# MCU.net
KiCad netlist of a schematic drawn in Altium Designer
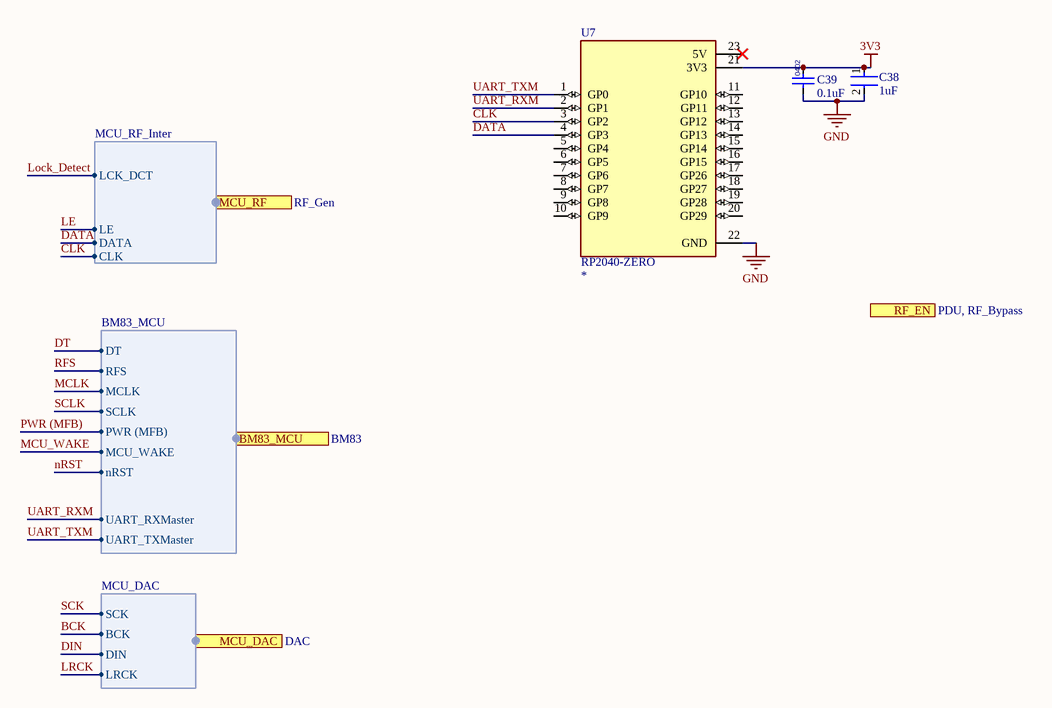
[diagram p0: MCU.SchDoc]

(export (version "E")
  (design (tool "Eeschema 10.0.6"))
  (components
    (comp (ref "C38")
      (value "1uF")
      (footprint "FP-GRM155-0_1-IPC_C")
      (libsource (lib "Altium Content Vault") (part "11868f565c42a9108669ba33697ecf6"))
    )
    (comp (ref "C39")
      (value "0.1uF")
      (footprint "FP-CC0402-IPC_B")
      (fields (field (name "TOLERANCE") "10%"))
      (libsource (lib "University of Wisconsin Formula FSAE") (part "0402 ceramic cap"))
    )
    (comp (ref "U7")
      (value "RP2040-ZERO")
      (footprint "MODULE_RP2040-ZERO")
      (description "Low-Cost, High-Performance Pico-Like MCU Board Based On Raspberry Pi Microcontroller RP2040")
      (fields (field (name "ALTIUM_VALUE") "*") (field (name "MF") "Waveshare Electronics"))
      (libsource (lib "University of Wisconsin Formula FSAE") (part "RP2040-ZERO"))
    )
  )
  (nets
    (net (code "5") (name "/CLK") (class "Default")
      (node (ref "U7") (pin "3") (pinfunction "GP2_3") (pintype "bidirectional"))
    )
    (net (code "6") (name "/DATA") (class "Default")
      (node (ref "U7") (pin "4") (pinfunction "GP3_4") (pintype "bidirectional"))
    )
    (net (code "19") (name "/UART_RXM") (class "Default")
      (node (ref "U7") (pin "2") (pinfunction "GP1_2") (pintype "bidirectional"))
    )
    (net (code "20") (name "/UART_TXM") (class "Default")
      (node (ref "U7") (pin "1") (pinfunction "GP0_1") (pintype "bidirectional"))
    )
    (net (code "25") (name "3V3") (class "Default")
      (node (ref "C38") (pin "1") (pinfunction "1_1") (pintype "passive"))
      (node (ref "C39") (pin "2") (pinfunction "2_2") (pintype "passive"))
      (node (ref "U7") (pin "21") (pinfunction "3V3_21") (pintype "power_in"))
    )
    (net (code "26") (name "GND") (class "Default")
      (node (ref "C38") (pin "2") (pinfunction "2_2") (pintype "passive"))
      (node (ref "C39") (pin "1") (pinfunction "1_1") (pintype "passive"))
      (node (ref "U7") (pin "22") (pinfunction "GND_22") (pintype "power_in"))
    )
    (net (code "27") (name "unconnected-(U7-5V-Pad23)") (class "Default")
      (node (ref "U7") (pin "23") (pinfunction "5V_23") (pintype "power_in+no_connect"))
    )
    (net (code "28") (name "unconnected-(U7-GP4-Pad5)") (class "Default")
      (node (ref "U7") (pin "5") (pinfunction "GP4_5") (pintype "bidirectional"))
    )
    (net (code "29") (name "unconnected-(U7-GP5-Pad6)") (class "Default")
      (node (ref "U7") (pin "6") (pinfunction "GP5_6") (pintype "bidirectional"))
    )
    (net (code "30") (name "unconnected-(U7-GP6-Pad7)") (class "Default")
      (node (ref "U7") (pin "7") (pinfunction "GP6_7") (pintype "bidirectional"))
    )
    (net (code "31") (name "unconnected-(U7-GP7-Pad8)") (class "Default")
      (node (ref "U7") (pin "8") (pinfunction "GP7_8") (pintype "bidirectional"))
    )
    (net (code "32") (name "unconnected-(U7-GP8-Pad9)") (class "Default")
      (node (ref "U7") (pin "9") (pinfunction "GP8_9") (pintype "bidirectional"))
    )
    (net (code "33") (name "unconnected-(U7-GP9-Pad10)") (class "Default")
      (node (ref "U7") (pin "10") (pinfunction "GP9_10") (pintype "bidirectional"))
    )
    (net (code "34") (name "unconnected-(U7-GP10-Pad11)") (class "Default")
      (node (ref "U7") (pin "11") (pinfunction "GP10_11") (pintype "bidirectional"))
    )
    (net (code "35") (name "unconnected-(U7-GP11-Pad12)") (class "Default")
      (node (ref "U7") (pin "12") (pinfunction "GP11_12") (pintype "bidirectional"))
    )
    (net (code "36") (name "unconnected-(U7-GP12-Pad13)") (class "Default")
      (node (ref "U7") (pin "13") (pinfunction "GP12_13") (pintype "bidirectional"))
    )
    (net (code "37") (name "unconnected-(U7-GP13-Pad14)") (class "Default")
      (node (ref "U7") (pin "14") (pinfunction "GP13_14") (pintype "bidirectional"))
    )
    (net (code "38") (name "unconnected-(U7-GP14-Pad15)") (class "Default")
      (node (ref "U7") (pin "15") (pinfunction "GP14_15") (pintype "bidirectional"))
    )
    (net (code "39") (name "unconnected-(U7-GP15-Pad16)") (class "Default")
      (node (ref "U7") (pin "16") (pinfunction "GP15_16") (pintype "bidirectional"))
    )
    (net (code "40") (name "unconnected-(U7-GP26-Pad17)") (class "Default")
      (node (ref "U7") (pin "17") (pinfunction "GP26_17") (pintype "bidirectional"))
    )
    (net (code "41") (name "unconnected-(U7-GP27-Pad18)") (class "Default")
      (node (ref "U7") (pin "18") (pinfunction "GP27_18") (pintype "bidirectional"))
    )
    (net (code "42") (name "unconnected-(U7-GP28-Pad19)") (class "Default")
      (node (ref "U7") (pin "19") (pinfunction "GP28_19") (pintype "bidirectional"))
    )
    (net (code "43") (name "unconnected-(U7-GP29-Pad20)") (class "Default")
      (node (ref "U7") (pin "20") (pinfunction "GP29_20") (pintype "bidirectional"))
    )
  )
)
